# PowerMeter.net
KiCad netlist of a schematic drawn in Altium Designer
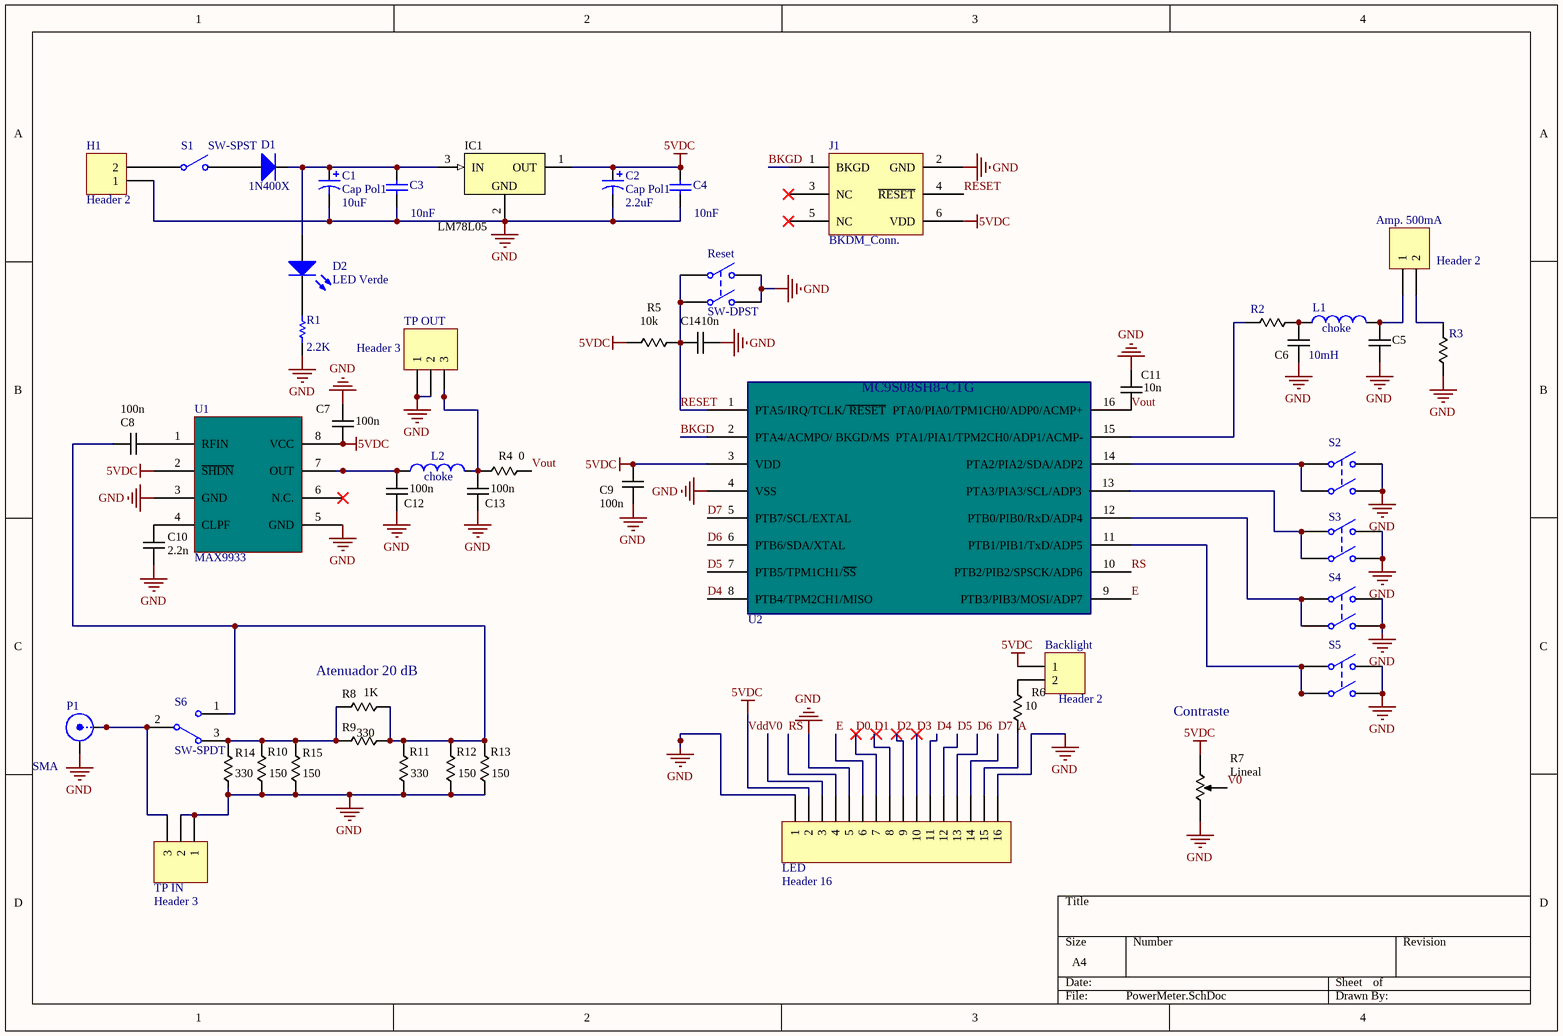
[diagram p0: PowerMeter.SchDoc]

(export (version "E")
  (design (tool "Eeschema 10.0.6"))
  (components
    (comp (ref "Amp. 500mA")
      (value "Header 2")
      (footprint "HDR1X2")
      (description "Header, 2-Pin")
      (fields (field (name "PUBLISHER") "Altium Limited"))
      (libsource (lib "") (part "Header 2_1"))
    )
    (comp (ref "Backlight")
      (value "Header 2")
      (footprint "HDR1X2")
      (description "Header, 2-Pin")
      (fields (field (name "PUBLISHER") "Altium Limited"))
      (libsource (lib "Miscellaneous Connectors") (part "Header 2"))
    )
    (comp (ref "C1")
      (value "Cap Pol1")
      (footprint "CAPPR2-5x11")
      (description "Polarized Capacitor (Radial)")
      (fields (field (name "ALTIUM_VALUE") "10uF") (field (name "PUBLISHER") "Altium Limited"))
      (libsource (lib "Miscellaneous Devices") (part "Cap Pol1"))
    )
    (comp (ref "C2")
      (value "Cap Pol1")
      (footprint "CAPPR2-5x11")
      (description "Polarized Capacitor (Radial)")
      (fields (field (name "ALTIUM_VALUE") "2.2uF") (field (name "PUBLISHER") "Altium Limited"))
      (libsource (lib "Miscellaneous Devices") (part "Cap Pol1"))
    )
    (comp (ref "C3")
      (value "10nF")
      (footprint "SMD generico")
      (description "Capacitor")
      (fields (field (name "PUBLISHER") "Altium Limited"))
      (libsource (lib "Miscellaneous Devices") (part "Cap"))
    )
    (comp (ref "C4")
      (value "10nF")
      (footprint "SMD generico")
      (description "Capacitor")
      (fields (field (name "PUBLISHER") "Altium Limited"))
      (libsource (lib "Miscellaneous Devices") (part "Cap"))
    )
    (comp (ref "C5")
      (value "Capacitor")
      (footprint "componentes:SMD Generico")
      (description "Capacitor no polarizado")
      (libsource (lib "Componentes") (part "Capacitor"))
    )
    (comp (ref "C6")
      (value "Capacitor")
      (footprint "componentes:SMD Generico")
      (description "Capacitor no polarizado")
      (libsource (lib "Componentes") (part "Capacitor"))
    )
    (comp (ref "C7")
      (value "Capacitor")
      (footprint "componentes:SMD Generico")
      (description "Capacitor no polarizado")
      (fields (field (name "CAPACIDAD") "100n"))
      (libsource (lib "Componentes") (part "Capacitor"))
    )
    (comp (ref "C8")
      (value "Capacitor")
      (footprint "componentes:SMD Generico")
      (description "Capacitor no polarizado")
      (fields (field (name "CAPACIDAD") "100n"))
      (libsource (lib "Componentes") (part "Capacitor"))
    )
    (comp (ref "C9")
      (value "Capacitor")
      (footprint "Componentes:CAP-0805")
      (description "Capacitor no polarizado")
      (fields (field (name "CAPACIDAD") "100n"))
      (libsource (lib "Componentes") (part "Capacitor"))
    )
    (comp (ref "C10")
      (value "Capacitor")
      (footprint "componentes:SMD Generico")
      (description "Capacitor no polarizado")
      (fields (field (name "CAPACIDAD") "2.2n"))
      (libsource (lib "Componentes") (part "Capacitor"))
    )
    (comp (ref "C11")
      (value "Capacitor")
      (footprint "componentes:SMD Generico")
      (description "Capacitor no polarizado")
      (fields (field (name "CAPACIDAD") "10n"))
      (libsource (lib "Componentes") (part "Capacitor"))
    )
    (comp (ref "C12")
      (value "Capacitor")
      (footprint "componentes:SMD Generico")
      (description "Capacitor no polarizado")
      (fields (field (name "CAPACIDAD") "100n"))
      (libsource (lib "Componentes") (part "Capacitor"))
    )
    (comp (ref "C13")
      (value "Capacitor")
      (footprint "componentes:SMD Generico")
      (description "Capacitor no polarizado")
      (fields (field (name "CAPACIDAD") "100n"))
      (libsource (lib "Componentes") (part "Capacitor"))
    )
    (comp (ref "C14")
      (value "Capacitor")
      (footprint "componentes:SMD Generico")
      (description "Capacitor no polarizado")
      (fields (field (name "CAPACIDAD") "10n"))
      (libsource (lib "Componentes") (part "Capacitor"))
    )
    (comp (ref "D1")
      (value "1N400X")
      (footprint "MELF")
      (description "Default Diode")
      (fields (field (name "PUBLISHER") "Altium Limited"))
      (libsource (lib "Miscellaneous Devices") (part "Diode"))
    )
    (comp (ref "D2")
      (value "LED Verde")
      (footprint "LED")
      (description "Typical INFRARED GaAs LED")
      (fields (field (name "PUBLISHER") "Altium Limited"))
      (libsource (lib "Miscellaneous Devices") (part "LED0"))
    )
    (comp (ref "H1")
      (value "Header 2")
      (footprint "HDR1X2")
      (description "Header, 2-Pin")
      (fields (field (name "PUBLISHER") "Altium Limited"))
      (libsource (lib "") (part "Header 2_2"))
    )
    (comp (ref "IC1")
      (value "78Lxx")
      (footprint "TO-92 (2)")
      (description "Regulador fijo de tensión positiva 100mA")
      (fields (field (name "NOMBRE") "LM78L05"))
      (libsource (lib "Circuitos integrados") (part "78Lxx"))
    )
    (comp (ref "J1")
      (value "BKDM_Conn.")
      (footprint "HDR2X3")
      (libsource (lib "Conectores") (part "BKDM_Conn."))
    )
    (comp (ref "L1")
      (value "choke")
      (footprint "axial-0.4")
      (description "Inductor")
      (fields (field (name "ALTIUM_VALUE") "10mH") (field (name "PUBLISHER") "Altium Limited"))
      (libsource (lib "Miscellaneous Devices") (part "Inductor"))
    )
    (comp (ref "L2")
      (value "choke")
      (footprint "AXIAL-0.4")
      (description "Inductor")
      (fields (field (name "PUBLISHER") "Altium Limited"))
      (libsource (lib "Miscellaneous Devices") (part "Inductor"))
    )
    (comp (ref "LED")
      (value "Header 16")
      (footprint "HDR1X16")
      (description "Header, 16-Pin")
      (fields (field (name "PUBLISHER") "Altium Limited"))
      (libsource (lib "Miscellaneous Connectors") (part "Header 16"))
    )
    (comp (ref "P1")
      (value "SMA")
      (footprint "SMB_V-RJ45")
      (description "SMB Straight Connector")
      (fields (field (name "PUBLISHER") "Altium Limited"))
      (libsource (lib "Miscellaneous Connectors") (part "SMB"))
    )
    (comp (ref "R1")
      (value "2.2K")
      (footprint "SMD generico")
      (description "Resistor")
      (fields (field (name "PUBLISHER") "Altium Limited"))
      (libsource (lib "Miscellaneous Devices") (part "Res1"))
    )
    (comp (ref "R2")
      (value "Resistor")
      (footprint "SMD generico")
      (libsource (lib "Componentes") (part "Resistor"))
    )
    (comp (ref "R3")
      (value "Resistor")
      (footprint "smd generico")
      (libsource (lib "Componentes") (part "Resistor"))
    )
    (comp (ref "R4")
      (value "Resistor")
      (footprint "SMD GENERICO")
      (fields (field (name "RESISTENCIA") "0"))
      (libsource (lib "Componentes") (part "Resistor"))
    )
    (comp (ref "R5")
      (value "Resistor")
      (footprint "smd generico")
      (fields (field (name "RESISTENCIA") "10k"))
      (libsource (lib "Componentes") (part "Resistor"))
    )
    (comp (ref "R6")
      (value "Resistor")
      (footprint "SMD generico")
      (fields (field (name "RESISTENCIA") "10"))
      (libsource (lib "Componentes") (part "Resistor"))
    )
    (comp (ref "R7")
      (value "Potenciómetro")
      (footprint "TRIMMER-H (5)")
      (fields (field (name "VARIACIÓN") "Lineal"))
      (libsource (lib "Componentes") (part "Potenciómetro"))
    )
    (comp (ref "R8")
      (value "Resistor")
      (footprint "SMD generico")
      (fields (field (name "RESISTENCIA") "1K"))
      (libsource (lib "Componentes") (part "Resistor"))
    )
    (comp (ref "R9")
      (value "Resistor")
      (footprint "SMD generico")
      (fields (field (name "RESISTENCIA") "330"))
      (libsource (lib "Componentes") (part "Resistor"))
    )
    (comp (ref "R10")
      (value "Resistor")
      (footprint "SMD generico")
      (fields (field (name "RESISTENCIA") "150"))
      (libsource (lib "Componentes") (part "Resistor"))
    )
    (comp (ref "R11")
      (value "Resistor")
      (footprint "SMD generico")
      (fields (field (name "RESISTENCIA") "330"))
      (libsource (lib "Componentes") (part "Resistor"))
    )
    (comp (ref "R12")
      (value "Resistor")
      (footprint "SMD generico")
      (fields (field (name "RESISTENCIA") "150"))
      (libsource (lib "Componentes") (part "Resistor"))
    )
    (comp (ref "R13")
      (value "Resistor")
      (footprint "SMD generico")
      (fields (field (name "RESISTENCIA") "150"))
      (libsource (lib "Componentes") (part "Resistor"))
    )
    (comp (ref "R14")
      (value "Resistor")
      (footprint "SMD generico")
      (fields (field (name "RESISTENCIA") "330"))
      (libsource (lib "Componentes") (part "Resistor"))
    )
    (comp (ref "R15")
      (value "Resistor")
      (footprint "SMD generico")
      (fields (field (name "RESISTENCIA") "150"))
      (libsource (lib "Componentes") (part "Resistor"))
    )
    (comp (ref "Reset")
      (value "SW-DPST")
      (footprint "SW-T-V-6x6")
      (description "Double-Pole, Single-Throw Switch")
      (fields (field (name "PUBLISHER") "Altium Limited"))
      (libsource (lib "Miscellaneous Devices") (part "SW-DPST"))
    )
    (comp (ref "S1")
      (value "SW-SPST")
      (footprint "SPST-2")
      (description "Single-Pole, Single-Throw Switch")
      (fields (field (name "PUBLISHER") "Altium Limited"))
      (libsource (lib "Miscellaneous Devices") (part "SW-SPST"))
    )
    (comp (ref "S2")
      (value "SW-DPST")
      (footprint "SW-T-V-6x6")
      (description "Double-Pole, Single-Throw Switch")
      (fields (field (name "PUBLISHER") "Altium Limited"))
      (libsource (lib "Miscellaneous Devices") (part "SW-DPST"))
    )
    (comp (ref "S3")
      (value "SW-DPST")
      (footprint "SW-T-V-6x6")
      (description "Double-Pole, Single-Throw Switch")
      (fields (field (name "PUBLISHER") "Altium Limited"))
      (libsource (lib "Miscellaneous Devices") (part "SW-DPST"))
    )
    (comp (ref "S4")
      (value "SW-DPST")
      (footprint "SW-T-V-6x6")
      (description "Double-Pole, Single-Throw Switch")
      (fields (field (name "PUBLISHER") "Altium Limited"))
      (libsource (lib "Miscellaneous Devices") (part "SW-DPST"))
    )
    (comp (ref "S5")
      (value "SW-DPST")
      (footprint "SW-T-V-6x6")
      (description "Double-Pole, Single-Throw Switch")
      (fields (field (name "PUBLISHER") "Altium Limited"))
      (libsource (lib "Miscellaneous Devices") (part "SW-DPST"))
    )
    (comp (ref "S6")
      (value "SW-SPDT")
      (footprint "SW-SPDT-H")
      (description "SPDT Subminiature Toggle Switch, Right Angle Mounting, Vertical Actuation")
      (fields (field (name "PUBLISHER") "Altium Limited"))
      (libsource (lib "Miscellaneous Devices") (part "SW-SPDT"))
    )
    (comp (ref "TP IN")
      (value "Header 3")
      (footprint "HDR1X3")
      (description "Header, 3-Pin")
      (fields (field (name "PUBLISHER") "Altium Limited"))
      (libsource (lib "") (part "Header 3_1"))
    )
    (comp (ref "TP OUT")
      (value "Header 3")
      (footprint "HDR1X3")
      (description "Header, 3-Pin")
      (fields (field (name "PUBLISHER") "Altium Limited"))
      (libsource (lib "Miscellaneous Connectors") (part "Header 3"))
    )
    (comp (ref "U1")
      (value "MAX9933")
      (footprint "Circuitos integrados:8L uMAX")
      (description "RF LOG DETECTOR")
      (fields (field (name "NAME") "MAX9933"))
      (libsource (lib "Circuitos integrados") (part "MAX9933"))
    )
    (comp (ref "U2")
      (value "MC9S08SH8")
      (footprint "TSSOP16")
      (description "Microcontrolador")
      (libsource (lib "Circuitos integrados") (part "MC9S08SH8"))
    )
  )
  (nets
    (net (code "1") (name "/A") (class "Default")
      (node (ref "LED") (pin "15") (pinfunction "15_15") (pintype "passive"))
      (node (ref "R6") (pin "1") (pinfunction "1_1") (pintype "passive"))
    )
    (net (code "2") (name "/BKGD") (class "Default")
      (node (ref "J1") (pin "1") (pinfunction "BKGD_1") (pintype "passive"))
      (node (ref "U2") (pin "2") (pinfunction "PTA4/ACMPO/_BKGD/MS_2") (pintype "passive"))
    )
    (net (code "3") (name "/D0") (class "Default")
      (node (ref "LED") (pin "7") (pinfunction "7_7") (pintype "passive+no_connect"))
    )
    (net (code "4") (name "/D1") (class "Default")
      (node (ref "LED") (pin "8") (pinfunction "8_8") (pintype "passive"))
    )
    (net (code "5") (name "/D2") (class "Default")
      (node (ref "LED") (pin "9") (pinfunction "9_9") (pintype "passive"))
    )
    (net (code "6") (name "/D3") (class "Default")
      (node (ref "LED") (pin "10") (pinfunction "10_10") (pintype "passive+no_connect"))
    )
    (net (code "7") (name "/D4") (class "Default")
      (node (ref "LED") (pin "11") (pinfunction "11_11") (pintype "passive"))
      (node (ref "U2") (pin "8") (pinfunction "PTB4/TPM2CH1/MISO_8") (pintype "passive"))
    )
    (net (code "8") (name "/D5") (class "Default")
      (node (ref "LED") (pin "12") (pinfunction "12_12") (pintype "passive"))
      (node (ref "U2") (pin "7") (pinfunction "PTB5/TPM1CH1/~{SS}_7") (pintype "passive"))
    )
    (net (code "9") (name "/D6") (class "Default")
      (node (ref "LED") (pin "13") (pinfunction "13_13") (pintype "passive"))
      (node (ref "U2") (pin "6") (pinfunction "PTB6/SDA/XTAL_6") (pintype "passive"))
    )
    (net (code "10") (name "/D7") (class "Default")
      (node (ref "LED") (pin "14") (pinfunction "14_14") (pintype "passive"))
      (node (ref "U2") (pin "5") (pinfunction "PTB7/SCL/EXTAL_5") (pintype "passive"))
    )
    (net (code "11") (name "/E") (class "Default")
      (node (ref "LED") (pin "6") (pinfunction "6_6") (pintype "passive"))
      (node (ref "U2") (pin "9") (pinfunction "PTB3/PIB3/MOSI/ADP7_9") (pintype "passive"))
    )
    (net (code "12") (name "/RESET") (class "Default")
      (node (ref "C14") (pin "2") (pinfunction "2_2") (pintype "passive"))
      (node (ref "J1") (pin "4") (pinfunction "RESET_4") (pintype "passive"))
      (node (ref "R5") (pin "1") (pinfunction "1_1") (pintype "passive"))
      (node (ref "Reset") (pin "1") (pinfunction "COMMON1_1") (pintype "passive"))
      (node (ref "Reset") (pin "3") (pinfunction "COMMON2_3") (pintype "passive"))
      (node (ref "U2") (pin "1") (pinfunction "PTA5/IRQ/TCLK/~{_RESET}_1") (pintype "passive"))
    )
    (net (code "13") (name "/RS") (class "Default")
      (node (ref "LED") (pin "4") (pinfunction "4_4") (pintype "passive"))
      (node (ref "U2") (pin "10") (pinfunction "PTB2/PIB2/SPSCK/ADP6_10") (pintype "passive"))
    )
    (net (code "14") (name "/V0") (class "Default")
      (node (ref "LED") (pin "3") (pinfunction "3_3") (pintype "passive"))
      (node (ref "R7") (pin "2") (pinfunction "M_2") (pintype "passive"))
    )
    (net (code "15") (name "/Vout") (class "Default")
      (node (ref "C11") (pin "1") (pinfunction "1_1") (pintype "passive"))
      (node (ref "R4") (pin "2") (pinfunction "2_2") (pintype "passive"))
      (node (ref "U2") (pin "16") (pinfunction "PTA0/PIA0/TPM1CH0/ADP0/ACMP+_16") (pintype "passive"))
    )
    (net (code "16") (name "5VDC") (class "Default")
      (node (ref "Backlight") (pin "1") (pinfunction "1_1") (pintype "passive"))
      (node (ref "C2") (pin "1") (pinfunction "1_1") (pintype "passive"))
      (node (ref "C4") (pin "2") (pinfunction "2_2") (pintype "passive"))
      (node (ref "C7") (pin "2") (pinfunction "2_2") (pintype "passive"))
      (node (ref "C9") (pin "2") (pinfunction "2_2") (pintype "passive"))
      (node (ref "IC1") (pin "1") (pinfunction "OUT_1") (pintype "power_in"))
      (node (ref "J1") (pin "6") (pinfunction "VDD_6") (pintype "passive"))
      (node (ref "LED") (pin "2") (pinfunction "2_2") (pintype "passive"))
      (node (ref "R5") (pin "2") (pinfunction "2_2") (pintype "passive"))
      (node (ref "R7") (pin "1") (pinfunction "1_1") (pintype "passive"))
      (node (ref "U1") (pin "2") (pinfunction "SHDN_2") (pintype "passive"))
      (node (ref "U1") (pin "8") (pinfunction "VCC_8") (pintype "passive"))
      (node (ref "U2") (pin "3") (pinfunction "VDD_3") (pintype "passive"))
    )
    (net (code "17") (name "GND") (class "Default")
      (node (ref "C1") (pin "2") (pinfunction "2_2") (pintype "passive"))
      (node (ref "C10") (pin "2") (pinfunction "2_2") (pintype "passive"))
      (node (ref "C11") (pin "2") (pinfunction "2_2") (pintype "passive"))
      (node (ref "C12") (pin "1") (pinfunction "1_1") (pintype "passive"))
      (node (ref "C13") (pin "1") (pinfunction "1_1") (pintype "passive"))
      (node (ref "C14") (pin "1") (pinfunction "1_1") (pintype "passive"))
      (node (ref "C2") (pin "2") (pinfunction "2_2") (pintype "passive"))
      (node (ref "C3") (pin "1") (pinfunction "1_1") (pintype "passive"))
      (node (ref "C4") (pin "1") (pinfunction "1_1") (pintype "passive"))
      (node (ref "C5") (pin "1") (pinfunction "1_1") (pintype "passive"))
      (node (ref "C6") (pin "1") (pinfunction "1_1") (pintype "passive"))
      (node (ref "C7") (pin "1") (pinfunction "1_1") (pintype "passive"))
      (node (ref "C9") (pin "1") (pinfunction "1_1") (pintype "passive"))
      (node (ref "H1") (pin "1") (pinfunction "1_1") (pintype "passive"))
      (node (ref "IC1") (pin "2") (pinfunction "GND_2") (pintype "power_in"))
      (node (ref "J1") (pin "2") (pinfunction "GND_2") (pintype "passive"))
      (node (ref "LED") (pin "1") (pinfunction "1_1") (pintype "passive"))
      (node (ref "LED") (pin "16") (pinfunction "16_16") (pintype "passive"))
      (node (ref "LED") (pin "5") (pinfunction "5_5") (pintype "passive"))
      (node (ref "P1") (pin "2") (pinfunction "Y_2") (pintype "passive"))
      (node (ref "R1") (pin "1") (pinfunction "1_1") (pintype "passive"))
      (node (ref "R10") (pin "1") (pinfunction "1_1") (pintype "passive"))
      (node (ref "R11") (pin "1") (pinfunction "1_1") (pintype "passive"))
      (node (ref "R12") (pin "1") (pinfunction "1_1") (pintype "passive"))
      (node (ref "R13") (pin "1") (pinfunction "1_1") (pintype "passive"))
      (node (ref "R14") (pin "1") (pinfunction "1_1") (pintype "passive"))
      (node (ref "R15") (pin "1") (pinfunction "1_1") (pintype "passive"))
      (node (ref "R3") (pin "1") (pinfunction "1_1") (pintype "passive"))
      (node (ref "R7") (pin "3") (pinfunction "2_3") (pintype "passive"))
      (node (ref "Reset") (pin "2") (pinfunction "NO1_2") (pintype "passive"))
      (node (ref "Reset") (pin "4") (pinfunction "NO2_4") (pintype "passive"))
      (node (ref "S2") (pin "2") (pinfunction "NO1_2") (pintype "passive"))
      (node (ref "S2") (pin "4") (pinfunction "NO2_4") (pintype "passive"))
      (node (ref "S3") (pin "2") (pinfunction "NO1_2") (pintype "passive"))
      (node (ref "S3") (pin "4") (pinfunction "NO2_4") (pintype "passive"))
      (node (ref "S4") (pin "2") (pinfunction "NO1_2") (pintype "passive"))
      (node (ref "S4") (pin "4") (pinfunction "NO2_4") (pintype "passive"))
      (node (ref "S5") (pin "2") (pinfunction "NO1_2") (pintype "passive"))
      (node (ref "S5") (pin "4") (pinfunction "NO2_4") (pintype "passive"))
      (node (ref "TP IN") (pin "1") (pinfunction "1_1") (pintype "passive"))
      (node (ref "TP IN") (pin "2") (pinfunction "2_2") (pintype "passive"))
      (node (ref "TP OUT") (pin "1") (pinfunction "1_1") (pintype "passive"))
      (node (ref "TP OUT") (pin "2") (pinfunction "2_2") (pintype "passive"))
      (node (ref "U1") (pin "3") (pinfunction "GND_3") (pintype "passive"))
      (node (ref "U1") (pin "5") (pinfunction "GND_5") (pintype "passive"))
      (node (ref "U2") (pin "4") (pinfunction "VSS_4") (pintype "passive"))
    )
    (net (code "18") (name "Net-(Amp. 500mA-Pad1)") (class "Default")
      (node (ref "Amp. 500mA") (pin "1") (pinfunction "1_1") (pintype "passive"))
      (node (ref "C5") (pin "2") (pinfunction "2_2") (pintype "passive"))
      (node (ref "L1") (pin "2") (pinfunction "2_2") (pintype "passive"))
    )
    (net (code "19") (name "Net-(Amp. 500mA-Pad2)") (class "Default")
      (node (ref "Amp. 500mA") (pin "2") (pinfunction "2_2") (pintype "passive"))
      (node (ref "R3") (pin "2") (pinfunction "2_2") (pintype "passive"))
    )
    (net (code "20") (name "Net-(Backlight-Pad2)") (class "Default")
      (node (ref "Backlight") (pin "2") (pinfunction "2_2") (pintype "passive"))
      (node (ref "R6") (pin "2") (pinfunction "2_2") (pintype "passive"))
    )
    (net (code "21") (name "Net-(C6-Pad2)") (class "Default")
      (node (ref "C6") (pin "2") (pinfunction "2_2") (pintype "passive"))
      (node (ref "L1") (pin "1") (pinfunction "1_1") (pintype "passive"))
      (node (ref "R2") (pin "1") (pinfunction "1_1") (pintype "passive"))
    )
    (net (code "22") (name "Net-(C8-Pad2)") (class "Default")
      (node (ref "C8") (pin "2") (pinfunction "2_2") (pintype "passive"))
      (node (ref "R11") (pin "2") (pinfunction "2_2") (pintype "passive"))
      (node (ref "R12") (pin "2") (pinfunction "2_2") (pintype "passive"))
      (node (ref "R13") (pin "2") (pinfunction "2_2") (pintype "passive"))
      (node (ref "R8") (pin "1") (pinfunction "1_1") (pintype "passive"))
      (node (ref "R9") (pin "1") (pinfunction "1_1") (pintype "passive"))
      (node (ref "S6") (pin "1") (pinfunction "1_1") (pintype "passive"))
    )
    (net (code "23") (name "Net-(C13-Pad2)") (class "Default")
      (node (ref "C13") (pin "2") (pinfunction "2_2") (pintype "passive"))
      (node (ref "L2") (pin "2") (pinfunction "2_2") (pintype "passive"))
      (node (ref "R4") (pin "1") (pinfunction "1_1") (pintype "passive"))
      (node (ref "TP OUT") (pin "3") (pinfunction "3_3") (pintype "passive"))
    )
    (net (code "24") (name "Net-(D1-A)") (class "Default")
      (node (ref "D1") (pin "1") (pinfunction "A_1") (pintype "passive"))
      (node (ref "S1") (pin "2") (pinfunction "NO_2") (pintype "passive"))
    )
    (net (code "25") (name "Net-(D1-K)") (class "Default")
      (node (ref "C1") (pin "1") (pinfunction "1_1") (pintype "passive"))
      (node (ref "C3") (pin "2") (pinfunction "2_2") (pintype "passive"))
      (node (ref "D1") (pin "2") (pinfunction "K_2") (pintype "passive"))
      (node (ref "D2") (pin "1") (pinfunction "A_1") (pintype "passive"))
      (node (ref "IC1") (pin "3") (pinfunction "IN_3") (pintype "input"))
    )
    (net (code "26") (name "Net-(D2-K)") (class "Default")
      (node (ref "D2") (pin "2") (pinfunction "K_2") (pintype "passive"))
      (node (ref "R1") (pin "2") (pinfunction "2_2") (pintype "passive"))
    )
    (net (code "27") (name "Net-(P1-X)") (class "Default")
      (node (ref "P1") (pin "1") (pinfunction "X_1") (pintype "passive"))
      (node (ref "S6") (pin "2") (pinfunction "2_2") (pintype "passive"))
      (node (ref "TP IN") (pin "3") (pinfunction "3_3") (pintype "passive"))
    )
    (net (code "28") (name "Net-(R10-Pad2)") (class "Default")
      (node (ref "R10") (pin "2") (pinfunction "2_2") (pintype "passive"))
      (node (ref "R14") (pin "2") (pinfunction "2_2") (pintype "passive"))
      (node (ref "R15") (pin "2") (pinfunction "2_2") (pintype "passive"))
      (node (ref "R8") (pin "2") (pinfunction "2_2") (pintype "passive"))
      (node (ref "R9") (pin "2") (pinfunction "2_2") (pintype "passive"))
      (node (ref "S6") (pin "3") (pinfunction "3_3") (pintype "passive"))
    )
    (net (code "29") (name "Net-(S1-COMMON)") (class "Default")
      (node (ref "H1") (pin "2") (pinfunction "2_2") (pintype "passive"))
      (node (ref "S1") (pin "1") (pinfunction "COMMON_1") (pintype "passive"))
    )
    (net (code "30") (name "Net-(S2-COMMON1)") (class "Default")
      (node (ref "S2") (pin "1") (pinfunction "COMMON1_1") (pintype "passive"))
      (node (ref "S2") (pin "3") (pinfunction "COMMON2_3") (pintype "passive"))
      (node (ref "U2") (pin "14") (pinfunction "PTA2/PIA2/SDA/ADP2_14") (pintype "passive"))
    )
    (net (code "31") (name "Net-(S3-COMMON1)") (class "Default")
      (node (ref "S3") (pin "1") (pinfunction "COMMON1_1") (pintype "passive"))
      (node (ref "S3") (pin "3") (pinfunction "COMMON2_3") (pintype "passive"))
      (node (ref "U2") (pin "13") (pinfunction "PTA3/PIA3/SCL/ADP3_13") (pintype "passive"))
    )
    (net (code "32") (name "Net-(S4-COMMON1)") (class "Default")
      (node (ref "S4") (pin "1") (pinfunction "COMMON1_1") (pintype "passive"))
      (node (ref "S4") (pin "3") (pinfunction "COMMON2_3") (pintype "passive"))
      (node (ref "U2") (pin "12") (pinfunction "PTB0/PIB0/RxD/ADP4_12") (pintype "passive"))
    )
    (net (code "33") (name "Net-(S5-COMMON1)") (class "Default")
      (node (ref "S5") (pin "1") (pinfunction "COMMON1_1") (pintype "passive"))
      (node (ref "S5") (pin "3") (pinfunction "COMMON2_3") (pintype "passive"))
      (node (ref "U2") (pin "11") (pinfunction "PTB1/PIB1/TxD/ADP5_11") (pintype "passive"))
    )
    (net (code "34") (name "Net-(U1-CLPF)") (class "Default")
      (node (ref "C10") (pin "1") (pinfunction "1_1") (pintype "passive"))
      (node (ref "U1") (pin "4") (pinfunction "CLPF_4") (pintype "passive"))
    )
    (net (code "35") (name "Net-(U1-OUT)") (class "Default")
      (node (ref "C12") (pin "2") (pinfunction "2_2") (pintype "passive"))
      (node (ref "L2") (pin "1") (pinfunction "1_1") (pintype "passive"))
      (node (ref "U1") (pin "7") (pinfunction "OUT_7") (pintype "passive"))
    )
    (net (code "36") (name "Net-(U1-RFIN)") (class "Default")
      (node (ref "C8") (pin "1") (pinfunction "1_1") (pintype "passive"))
      (node (ref "U1") (pin "1") (pinfunction "RFIN_1") (pintype "passive"))
    )
    (net (code "37") (name "Net-(U2-PTA1{slash}PIA1{slash}TPM2CH0{slash}ADP1{slash}ACMP-)") (class "Default")
      (node (ref "R2") (pin "2") (pinfunction "2_2") (pintype "passive"))
      (node (ref "U2") (pin "15") (pinfunction "PTA1/PIA1/TPM2CH0/ADP1/ACMP-_15") (pintype "passive"))
    )
    (net (code "38") (name "unconnected-(J1-NC-Pad3)") (class "Default")
      (node (ref "J1") (pin "3") (pinfunction "NC_3") (pintype "passive+no_connect"))
    )
    (net (code "39") (name "unconnected-(J1-NC-Pad5)") (class "Default")
      (node (ref "J1") (pin "5") (pinfunction "NC_5") (pintype "passive+no_connect"))
    )
    (net (code "40") (name "unconnected-(U1-N.C.-Pad6)") (class "Default")
      (node (ref "U1") (pin "6") (pinfunction "N.C._6") (pintype "passive+no_connect"))
    )
  )
)
